# xbeeDemoXmit.net
KiCad netlist of a schematic drawn in EAGLE
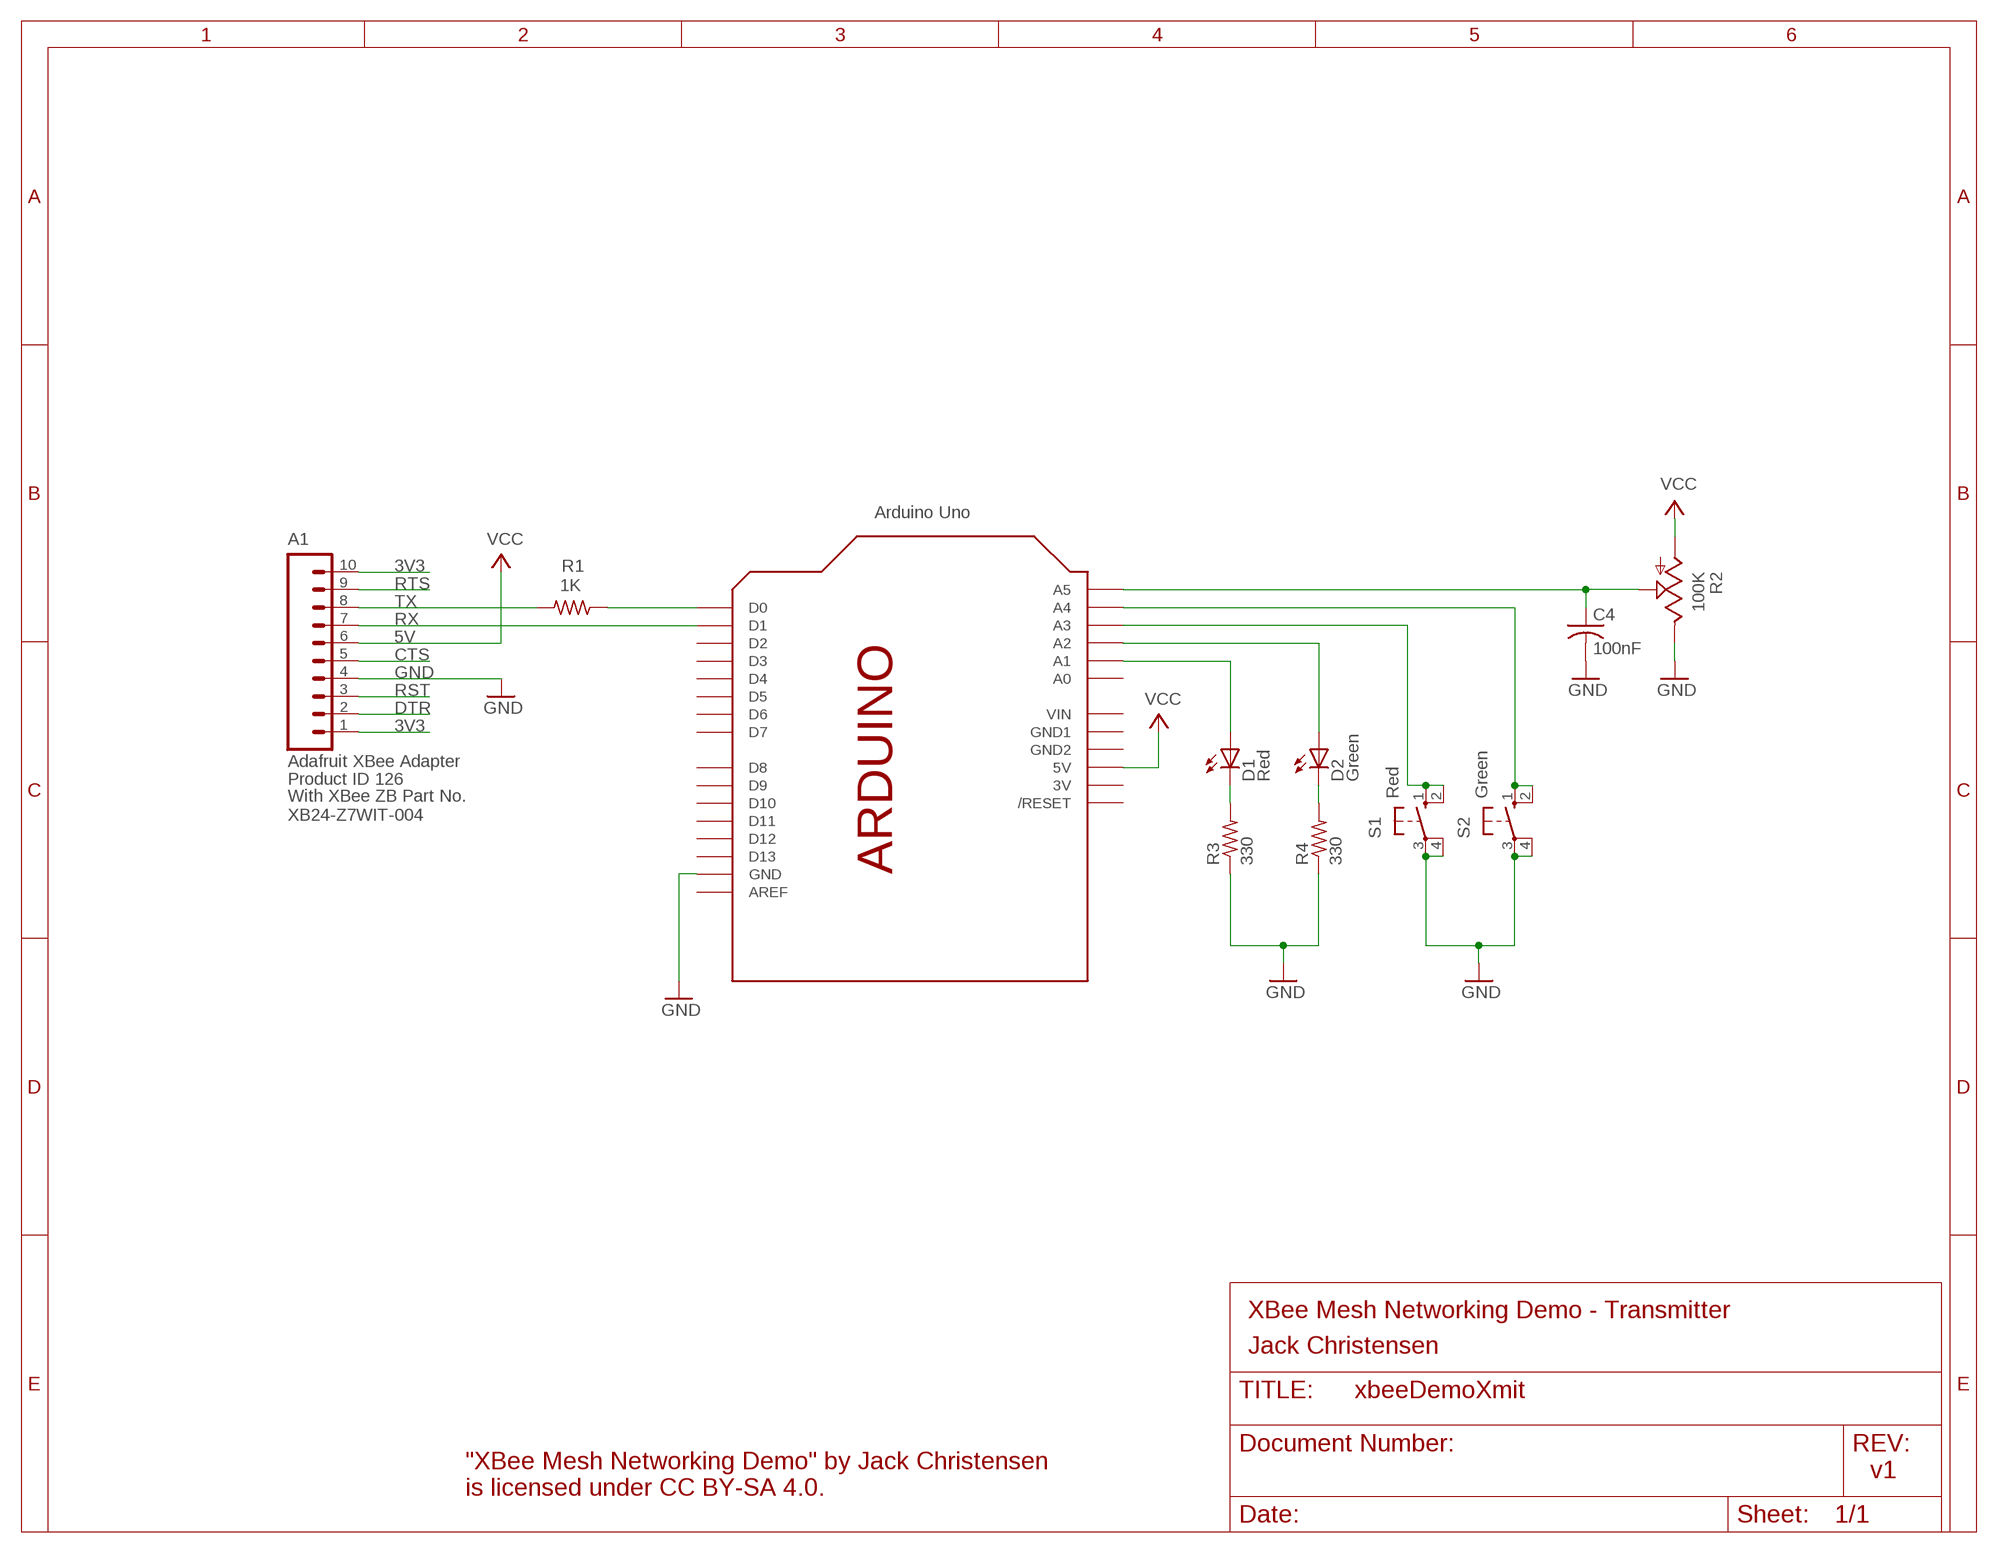
[diagram p0: schematic, sheet 1]

(export (version "E")
  (design (tool "Eeschema 10.0.6"))
  (components
    (comp (ref "A1")
      (value "Adafruit XBee Adapter")
      (footprint "eagle-import:1X10_LOCK")
      (libsource (lib "eagle-import") (part "M10LOCK"))
    )
    (comp (ref "C4")
      (value "100nF")
      (footprint "eagle-import:M0805")
      (libsource (lib "eagle-import") (part "C-USM0805"))
    )
    (comp (ref "D1")
      (value "Red")
      (footprint "eagle-import:LED5MM")
      (libsource (lib "eagle-import") (part "LED5MM"))
    )
    (comp (ref "D2")
      (value "Green")
      (footprint "eagle-import:LED5MM")
      (libsource (lib "eagle-import") (part "LED5MM"))
    )
    (comp (ref "R1")
      (value "1K")
      (footprint "eagle-import:M0805")
      (libsource (lib "eagle-import") (part "R-US_M0805"))
    )
    (comp (ref "R2")
      (value "100K")
      (footprint "eagle-import:TRIMPOT-3386P")
      (libsource (lib "eagle-import") (part "TRIMPOT3386P"))
    )
    (comp (ref "R3")
      (value "330")
      (footprint "eagle-import:M0805")
      (libsource (lib "eagle-import") (part "R-US_M0805"))
    )
    (comp (ref "R4")
      (value "330")
      (footprint "eagle-import:M0805")
      (libsource (lib "eagle-import") (part "R-US_M0805"))
    )
    (comp (ref "S1")
      (value "Red")
      (footprint "eagle-import:B3F-10XXOCT")
      (libsource (lib "eagle-import") (part "10-XXOCT"))
    )
    (comp (ref "S2")
      (value "Green")
      (footprint "eagle-import:B3F-10XXOCT")
      (libsource (lib "eagle-import") (part "10-XXOCT"))
    )
    (comp (ref "U$1")
      (value "ARDUINOUNO")
      (footprint "eagle-import:ARDUINO")
      (libsource (lib "eagle-import") (part "ARDUINOUNO"))
    )
  )
  (nets
    (net (code "1") (name "/3V") (class "Default")
      (node (ref "U$1") (pin "3V") (pinfunction "3V_3V") (pintype "power_in"))
    )
    (net (code "2") (name "/GND1") (class "Default")
      (node (ref "U$1") (pin "GND1") (pinfunction "GND1_GND1") (pintype "power_in"))
    )
    (net (code "3") (name "/GND2") (class "Default")
      (node (ref "U$1") (pin "GND2") (pinfunction "GND2_GND2") (pintype "power_in"))
    )
    (net (code "4") (name "/VIN") (class "Default")
      (node (ref "U$1") (pin "VIN") (pinfunction "VIN_VIN") (pintype "power_in"))
    )
    (net (code "5") (name "GND") (class "Default")
      (node (ref "A1") (pin "4") (pinfunction "4_4") (pintype "passive"))
      (node (ref "C4") (pin "2") (pinfunction "2_2") (pintype "passive"))
      (node (ref "R2") (pin "1") (pinfunction "E_1") (pintype "passive"))
      (node (ref "R3") (pin "1") (pinfunction "1_1") (pintype "passive"))
      (node (ref "R4") (pin "1") (pinfunction "1_1") (pintype "passive"))
      (node (ref "S1") (pin "3") (pinfunction "P_3") (pintype "passive"))
      (node (ref "S1") (pin "4") (pinfunction "P1_4") (pintype "passive"))
      (node (ref "S2") (pin "3") (pinfunction "P_3") (pintype "passive"))
      (node (ref "S2") (pin "4") (pinfunction "P1_4") (pintype "passive"))
      (node (ref "U$1") (pin "GND") (pinfunction "GND_GND") (pintype "power_in"))
    )
    (net (code "6") (name "Net-(A1-Pad7)") (class "Default")
      (node (ref "A1") (pin "7") (pinfunction "7_7") (pintype "passive"))
      (node (ref "U$1") (pin "D1") (pinfunction "D1_D1") (pintype "bidirectional"))
    )
    (net (code "7") (name "Net-(A1-Pad8)") (class "Default")
      (node (ref "A1") (pin "8") (pinfunction "8_8") (pintype "passive"))
      (node (ref "R1") (pin "2") (pinfunction "2_2") (pintype "passive"))
    )
    (net (code "8") (name "Net-(D1-C)") (class "Default")
      (node (ref "D1") (pin "K") (pinfunction "C_K") (pintype "passive"))
      (node (ref "R3") (pin "2") (pinfunction "2_2") (pintype "passive"))
    )
    (net (code "9") (name "Net-(D1-PadA)") (class "Default")
      (node (ref "D1") (pin "A") (pinfunction "A_A") (pintype "passive"))
      (node (ref "U$1") (pin "A1") (pinfunction "A1_A1") (pintype "bidirectional"))
    )
    (net (code "10") (name "Net-(D2-C)") (class "Default")
      (node (ref "D2") (pin "K") (pinfunction "C_K") (pintype "passive"))
      (node (ref "R4") (pin "2") (pinfunction "2_2") (pintype "passive"))
    )
    (net (code "11") (name "Net-(D2-PadA)") (class "Default")
      (node (ref "D2") (pin "A") (pinfunction "A_A") (pintype "passive"))
      (node (ref "U$1") (pin "A2") (pinfunction "A2_A2") (pintype "bidirectional"))
    )
    (net (code "12") (name "Net-(R1-Pad1)") (class "Default")
      (node (ref "R1") (pin "1") (pinfunction "1_1") (pintype "passive"))
      (node (ref "U$1") (pin "D0") (pinfunction "D0_D0") (pintype "bidirectional"))
    )
    (net (code "13") (name "Net-(R2-S)") (class "Default")
      (node (ref "C4") (pin "1") (pinfunction "1_1") (pintype "passive"))
      (node (ref "R2") (pin "2") (pinfunction "S_2") (pintype "passive"))
      (node (ref "U$1") (pin "A5") (pinfunction "A5_A5") (pintype "bidirectional"))
    )
    (net (code "14") (name "Net-(S1-S)") (class "Default")
      (node (ref "S1") (pin "1") (pinfunction "S_1") (pintype "passive"))
      (node (ref "S1") (pin "2") (pinfunction "S1_2") (pintype "passive"))
      (node (ref "U$1") (pin "A3") (pinfunction "A3_A3") (pintype "bidirectional"))
    )
    (net (code "15") (name "Net-(S2-S)") (class "Default")
      (node (ref "S2") (pin "1") (pinfunction "S_1") (pintype "passive"))
      (node (ref "S2") (pin "2") (pinfunction "S1_2") (pintype "passive"))
      (node (ref "U$1") (pin "A4") (pinfunction "A4_A4") (pintype "bidirectional"))
    )
    (net (code "16") (name "VCC") (class "Default")
      (node (ref "A1") (pin "6") (pinfunction "6_6") (pintype "passive"))
      (node (ref "R2") (pin "3") (pinfunction "A_3") (pintype "passive"))
      (node (ref "U$1") (pin "5V") (pinfunction "5V_5V") (pintype "power_in"))
    )
    (net (code "17") (name "unconnected-(A1-Pad1)") (class "Default")
      (node (ref "A1") (pin "1") (pinfunction "1_1") (pintype "passive"))
    )
    (net (code "18") (name "unconnected-(A1-Pad2)") (class "Default")
      (node (ref "A1") (pin "2") (pinfunction "2_2") (pintype "passive"))
    )
    (net (code "19") (name "unconnected-(A1-Pad3)") (class "Default")
      (node (ref "A1") (pin "3") (pinfunction "3_3") (pintype "passive"))
    )
    (net (code "20") (name "unconnected-(A1-Pad5)") (class "Default")
      (node (ref "A1") (pin "5") (pinfunction "5_5") (pintype "passive"))
    )
    (net (code "21") (name "unconnected-(A1-Pad9)") (class "Default")
      (node (ref "A1") (pin "9") (pinfunction "9_9") (pintype "passive"))
    )
    (net (code "22") (name "unconnected-(A1-Pad10)") (class "Default")
      (node (ref "A1") (pin "10") (pinfunction "10_10") (pintype "passive"))
    )
    (net (code "23") (name "unconnected-(U$1-PadA0)") (class "Default")
      (node (ref "U$1") (pin "A0") (pinfunction "A0_A0") (pintype "bidirectional"))
    )
    (net (code "24") (name "unconnected-(U$1-PadAREF)") (class "Default")
      (node (ref "U$1") (pin "AREF") (pinfunction "AREF_AREF") (pintype "bidirectional"))
    )
    (net (code "25") (name "unconnected-(U$1-PadD2)") (class "Default")
      (node (ref "U$1") (pin "D2") (pinfunction "D2_D2") (pintype "bidirectional"))
    )
    (net (code "26") (name "unconnected-(U$1-PadD3)") (class "Default")
      (node (ref "U$1") (pin "D3") (pinfunction "D3_D3") (pintype "bidirectional"))
    )
    (net (code "27") (name "unconnected-(U$1-PadD4)") (class "Default")
      (node (ref "U$1") (pin "D4") (pinfunction "D4_D4") (pintype "bidirectional"))
    )
    (net (code "28") (name "unconnected-(U$1-PadD5)") (class "Default")
      (node (ref "U$1") (pin "D5") (pinfunction "D5_D5") (pintype "bidirectional"))
    )
    (net (code "29") (name "unconnected-(U$1-PadD6)") (class "Default")
      (node (ref "U$1") (pin "D6") (pinfunction "D6_D6") (pintype "bidirectional"))
    )
    (net (code "30") (name "unconnected-(U$1-PadD7)") (class "Default")
      (node (ref "U$1") (pin "D7") (pinfunction "D7_D7") (pintype "bidirectional"))
    )
    (net (code "31") (name "unconnected-(U$1-PadD8)") (class "Default")
      (node (ref "U$1") (pin "D8") (pinfunction "D8_D8") (pintype "bidirectional"))
    )
    (net (code "32") (name "unconnected-(U$1-PadD9)") (class "Default")
      (node (ref "U$1") (pin "D9") (pinfunction "D9_D9") (pintype "bidirectional"))
    )
    (net (code "33") (name "unconnected-(U$1-PadD10)") (class "Default")
      (node (ref "U$1") (pin "D10") (pinfunction "D10_D10") (pintype "bidirectional"))
    )
    (net (code "34") (name "unconnected-(U$1-PadD11)") (class "Default")
      (node (ref "U$1") (pin "D11") (pinfunction "D11_D11") (pintype "bidirectional"))
    )
    (net (code "35") (name "unconnected-(U$1-PadD12)") (class "Default")
      (node (ref "U$1") (pin "D12") (pinfunction "D12_D12") (pintype "bidirectional"))
    )
    (net (code "36") (name "unconnected-(U$1-PadD13)") (class "Default")
      (node (ref "U$1") (pin "D13") (pinfunction "D13_D13") (pintype "bidirectional"))
    )
    (net (code "37") (name "unconnected-(U$1-{slash}RESET-PadRESET)") (class "Default")
      (node (ref "U$1") (pin "RESET") (pinfunction "/RESET_RESET") (pintype "bidirectional"))
    )
  )
)
